# Boot_selector_SMD.net
KiCad netlist of a schematic drawn in EAGLE
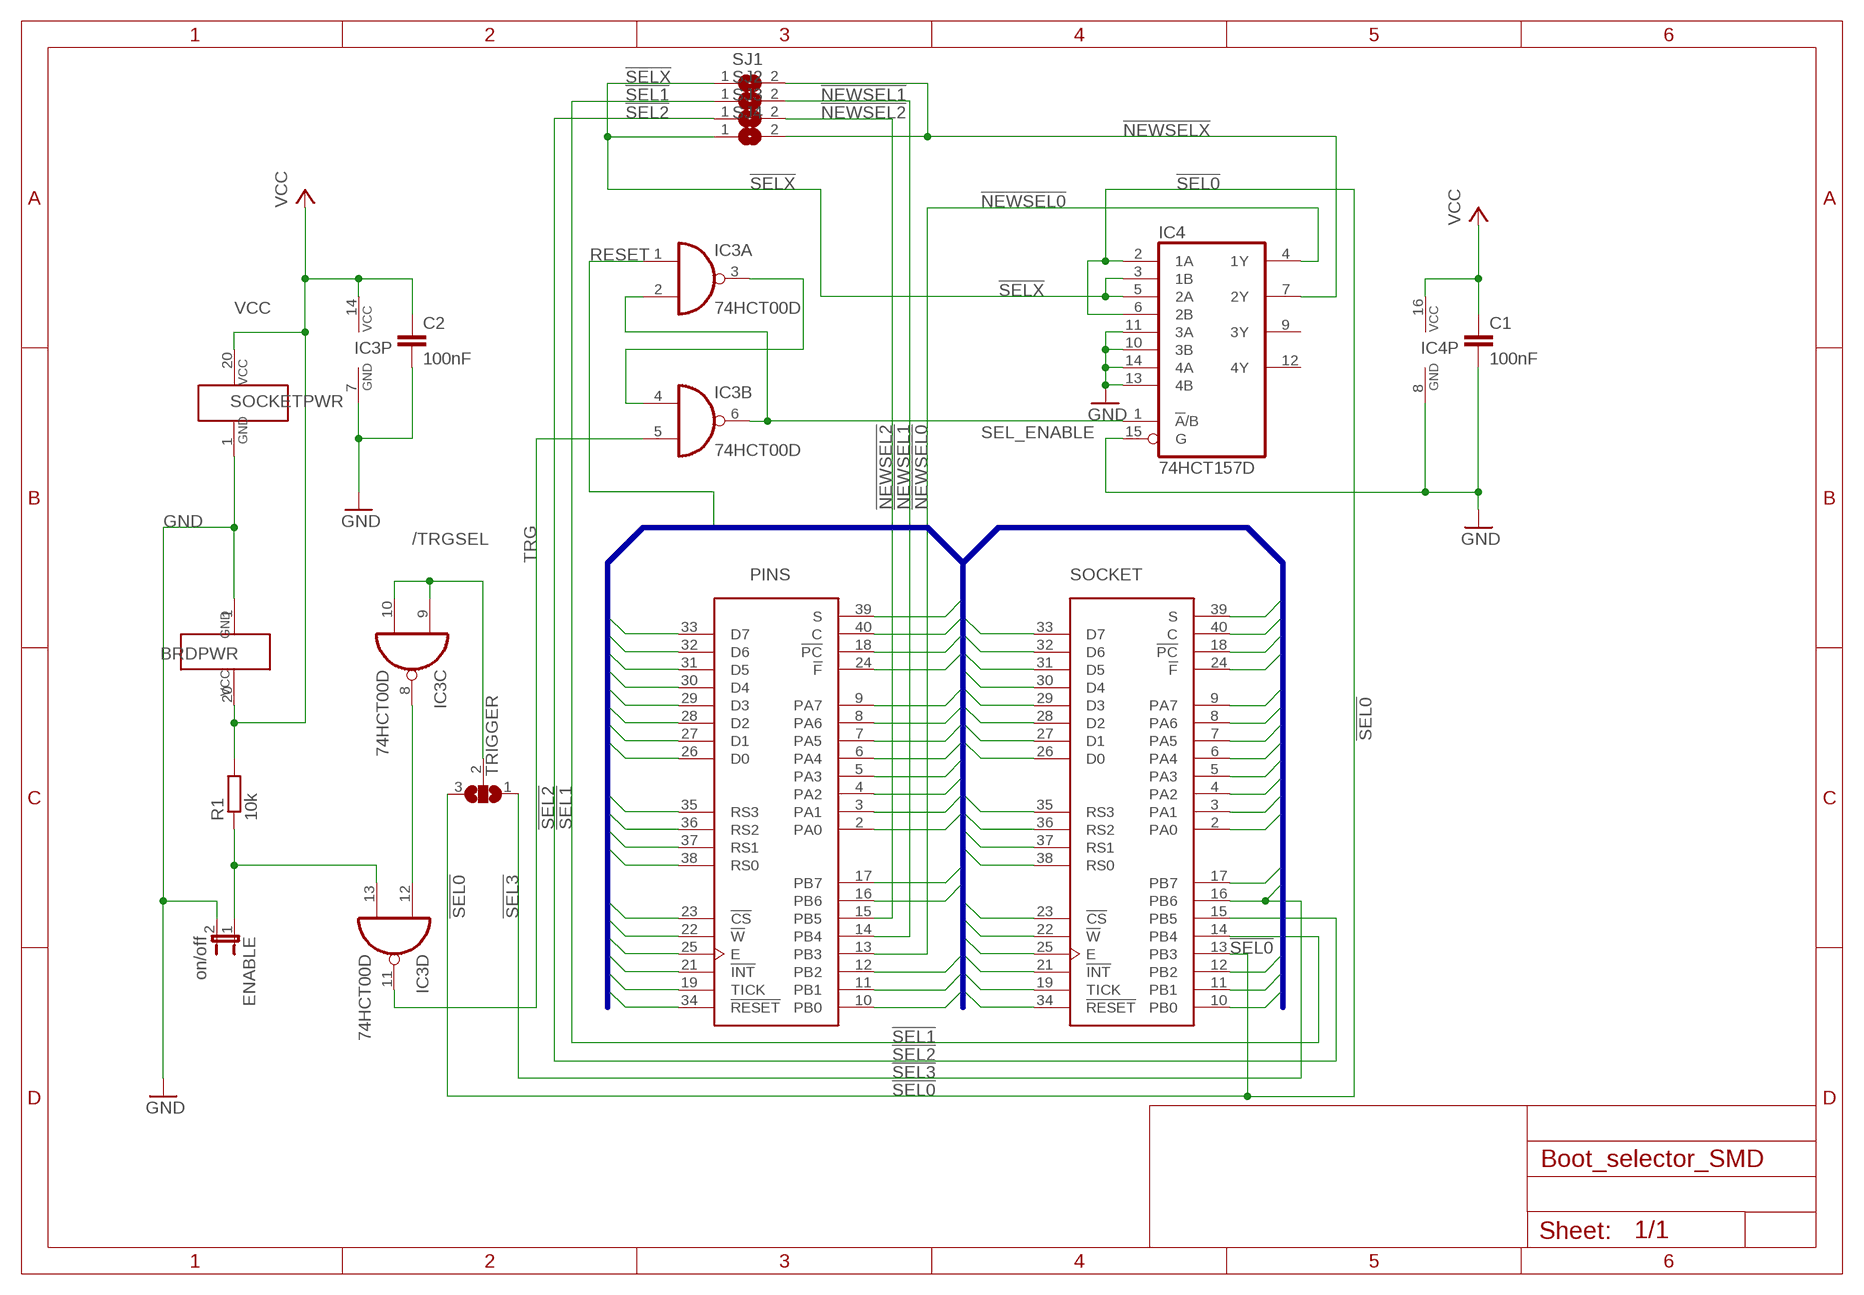
[diagram p0: schematic, sheet 1]

(export (version "E")
  (design (tool "Eeschema 10.0.6"))
  (components
    (comp (ref "BRD")
      (value "PINS")
      (footprint "eagle-import:DIP40-6")
      (libsource (lib "eagle-import") (part "CIA_DIP"))
    )
    (comp (ref "C1")
      (value "100nF")
      (footprint "eagle-import:C0805")
      (libsource (lib "eagle-import") (part "C-EUC0805"))
    )
    (comp (ref "C2")
      (value "100nF")
      (footprint "eagle-import:C0805K")
      (libsource (lib "eagle-import") (part "C-EUC0805K"))
    )
    (comp (ref "ENABLE")
      (value "on/off")
      (footprint "eagle-import:JP1")
      (libsource (lib "eagle-import") (part "JP1E"))
    )
    (comp (ref "IC3")
      (value "74HCT00D")
      (footprint "eagle-import:SO14")
      (libsource (lib "eagle-import") (part "7400DHCT"))
    )
    (comp (ref "IC4")
      (value "74HCT157D")
      (footprint "eagle-import:SO16")
      (libsource (lib "eagle-import") (part "74157DHCT"))
    )
    (comp (ref "R1")
      (value "10k")
      (footprint "eagle-import:R0805")
      (libsource (lib "eagle-import") (part "R-EU_R0805"))
    )
    (comp (ref "SJ1") (value "SJ") (footprint "eagle-import:SJ") (libsource (lib "eagle-import") (part "SJ")))
    (comp (ref "SJ2") (value "SJ") (footprint "eagle-import:SJ") (libsource (lib "eagle-import") (part "SJ")))
    (comp (ref "SJ3") (value "SJ") (footprint "eagle-import:SJ") (libsource (lib "eagle-import") (part "SJ")))
    (comp (ref "SJ4") (value "SJ") (footprint "eagle-import:SJ") (libsource (lib "eagle-import") (part "SJ")))
    (comp (ref "SOCKET")
      (value "CIA_DIP")
      (footprint "eagle-import:DIP40-6")
      (libsource (lib "eagle-import") (part "CIA_DIP"))
    )
    (comp (ref "TRIGGER")
      (value "SJ2W")
      (footprint "eagle-import:SJ_2")
      (libsource (lib "eagle-import") (part "SJ2W"))
    )
  )
  (nets
    (net (code "1") (name "/C") (class "Default")
      (node (ref "BRD") (pin "40") (pinfunction "C_40") (pintype "bidirectional"))
      (node (ref "SOCKET") (pin "40") (pinfunction "C_40") (pintype "bidirectional"))
    )
    (net (code "2") (name "/CS") (class "Default")
      (node (ref "BRD") (pin "23") (pinfunction "~{CS}_23") (pintype "input"))
      (node (ref "SOCKET") (pin "23") (pinfunction "~{CS}_23") (pintype "input"))
    )
    (net (code "3") (name "/D0") (class "Default")
      (node (ref "BRD") (pin "26") (pinfunction "D0_26") (pintype "bidirectional"))
      (node (ref "SOCKET") (pin "26") (pinfunction "D0_26") (pintype "bidirectional"))
    )
    (net (code "4") (name "/D1") (class "Default")
      (node (ref "BRD") (pin "27") (pinfunction "D1_27") (pintype "bidirectional"))
      (node (ref "SOCKET") (pin "27") (pinfunction "D1_27") (pintype "bidirectional"))
    )
    (net (code "5") (name "/D2") (class "Default")
      (node (ref "BRD") (pin "28") (pinfunction "D2_28") (pintype "bidirectional"))
      (node (ref "SOCKET") (pin "28") (pinfunction "D2_28") (pintype "bidirectional"))
    )
    (net (code "6") (name "/D3") (class "Default")
      (node (ref "BRD") (pin "29") (pinfunction "D3_29") (pintype "bidirectional"))
      (node (ref "SOCKET") (pin "29") (pinfunction "D3_29") (pintype "bidirectional"))
    )
    (net (code "7") (name "/D4") (class "Default")
      (node (ref "BRD") (pin "30") (pinfunction "D4_30") (pintype "bidirectional"))
      (node (ref "SOCKET") (pin "30") (pinfunction "D4_30") (pintype "bidirectional"))
    )
    (net (code "8") (name "/D5") (class "Default")
      (node (ref "BRD") (pin "31") (pinfunction "D5_31") (pintype "bidirectional"))
      (node (ref "SOCKET") (pin "31") (pinfunction "D5_31") (pintype "bidirectional"))
    )
    (net (code "9") (name "/D6") (class "Default")
      (node (ref "BRD") (pin "32") (pinfunction "D6_32") (pintype "bidirectional"))
      (node (ref "SOCKET") (pin "32") (pinfunction "D6_32") (pintype "bidirectional"))
    )
    (net (code "10") (name "/D7") (class "Default")
      (node (ref "BRD") (pin "33") (pinfunction "D7_33") (pintype "bidirectional"))
      (node (ref "SOCKET") (pin "33") (pinfunction "D7_33") (pintype "bidirectional"))
    )
    (net (code "11") (name "/E") (class "Default")
      (node (ref "BRD") (pin "25") (pinfunction "E_25") (pintype "input"))
      (node (ref "SOCKET") (pin "25") (pinfunction "E_25") (pintype "input"))
    )
    (net (code "12") (name "/F") (class "Default")
      (node (ref "BRD") (pin "24") (pinfunction "~{F}_24") (pintype "bidirectional"))
      (node (ref "SOCKET") (pin "24") (pinfunction "~{F}_24") (pintype "bidirectional"))
    )
    (net (code "13") (name "/INT") (class "Default")
      (node (ref "BRD") (pin "21") (pinfunction "~{INT}_21") (pintype "output"))
      (node (ref "SOCKET") (pin "21") (pinfunction "~{INT}_21") (pintype "output"))
    )
    (net (code "14") (name "/PA0") (class "Default")
      (node (ref "BRD") (pin "2") (pinfunction "PA0_2") (pintype "bidirectional"))
      (node (ref "SOCKET") (pin "2") (pinfunction "PA0_2") (pintype "bidirectional"))
    )
    (net (code "15") (name "/PA1") (class "Default")
      (node (ref "BRD") (pin "3") (pinfunction "PA1_3") (pintype "bidirectional"))
      (node (ref "SOCKET") (pin "3") (pinfunction "PA1_3") (pintype "bidirectional"))
    )
    (net (code "16") (name "/PA2") (class "Default")
      (node (ref "BRD") (pin "4") (pinfunction "PA2_4") (pintype "bidirectional"))
      (node (ref "SOCKET") (pin "4") (pinfunction "PA2_4") (pintype "bidirectional"))
    )
    (net (code "17") (name "/PA3") (class "Default")
      (node (ref "BRD") (pin "5") (pinfunction "PA3_5") (pintype "bidirectional"))
      (node (ref "SOCKET") (pin "5") (pinfunction "PA3_5") (pintype "bidirectional"))
    )
    (net (code "18") (name "/PA4") (class "Default")
      (node (ref "BRD") (pin "6") (pinfunction "PA4_6") (pintype "bidirectional"))
      (node (ref "SOCKET") (pin "6") (pinfunction "PA4_6") (pintype "bidirectional"))
    )
    (net (code "19") (name "/PA5") (class "Default")
      (node (ref "BRD") (pin "7") (pinfunction "PA5_7") (pintype "bidirectional"))
      (node (ref "SOCKET") (pin "7") (pinfunction "PA5_7") (pintype "bidirectional"))
    )
    (net (code "20") (name "/PA6") (class "Default")
      (node (ref "BRD") (pin "8") (pinfunction "PA6_8") (pintype "bidirectional"))
      (node (ref "SOCKET") (pin "8") (pinfunction "PA6_8") (pintype "bidirectional"))
    )
    (net (code "21") (name "/PA7") (class "Default")
      (node (ref "BRD") (pin "9") (pinfunction "PA7_9") (pintype "bidirectional"))
      (node (ref "SOCKET") (pin "9") (pinfunction "PA7_9") (pintype "bidirectional"))
    )
    (net (code "22") (name "/PB0") (class "Default")
      (node (ref "BRD") (pin "10") (pinfunction "PB0_10") (pintype "bidirectional"))
      (node (ref "SOCKET") (pin "10") (pinfunction "PB0_10") (pintype "bidirectional"))
    )
    (net (code "23") (name "/PB1") (class "Default")
      (node (ref "BRD") (pin "11") (pinfunction "PB1_11") (pintype "bidirectional"))
      (node (ref "SOCKET") (pin "11") (pinfunction "PB1_11") (pintype "bidirectional"))
    )
    (net (code "24") (name "/PB2") (class "Default")
      (node (ref "BRD") (pin "12") (pinfunction "PB2_12") (pintype "bidirectional"))
      (node (ref "SOCKET") (pin "12") (pinfunction "PB2_12") (pintype "bidirectional"))
    )
    (net (code "25") (name "/PB7") (class "Default")
      (node (ref "BRD") (pin "17") (pinfunction "PB7_17") (pintype "bidirectional"))
      (node (ref "SOCKET") (pin "17") (pinfunction "PB7_17") (pintype "bidirectional"))
    )
    (net (code "26") (name "/PC") (class "Default")
      (node (ref "BRD") (pin "18") (pinfunction "~{PC}_18") (pintype "bidirectional"))
      (node (ref "SOCKET") (pin "18") (pinfunction "~{PC}_18") (pintype "bidirectional"))
    )
    (net (code "27") (name "/RESET") (class "Default")
      (node (ref "BRD") (pin "34") (pinfunction "~{RESET}_34") (pintype "input"))
      (node (ref "IC3") (pin "1") (pinfunction "I0_1") (pintype "input"))
      (node (ref "SOCKET") (pin "34") (pinfunction "~{RESET}_34") (pintype "input"))
    )
    (net (code "28") (name "/RS0") (class "Default")
      (node (ref "BRD") (pin "38") (pinfunction "RS0_38") (pintype "input"))
      (node (ref "SOCKET") (pin "38") (pinfunction "RS0_38") (pintype "input"))
    )
    (net (code "29") (name "/RS1") (class "Default")
      (node (ref "BRD") (pin "37") (pinfunction "RS1_37") (pintype "input"))
      (node (ref "SOCKET") (pin "37") (pinfunction "RS1_37") (pintype "input"))
    )
    (net (code "30") (name "/RS2") (class "Default")
      (node (ref "BRD") (pin "36") (pinfunction "RS2_36") (pintype "input"))
      (node (ref "SOCKET") (pin "36") (pinfunction "RS2_36") (pintype "input"))
    )
    (net (code "31") (name "/RS3") (class "Default")
      (node (ref "BRD") (pin "35") (pinfunction "RS3_35") (pintype "input"))
      (node (ref "SOCKET") (pin "35") (pinfunction "RS3_35") (pintype "input"))
    )
    (net (code "32") (name "/S") (class "Default")
      (node (ref "BRD") (pin "39") (pinfunction "S_39") (pintype "bidirectional"))
      (node (ref "SOCKET") (pin "39") (pinfunction "S_39") (pintype "bidirectional"))
    )
    (net (code "33") (name "/SEL_ENABLE") (class "Default")
      (node (ref "IC3") (pin "2") (pinfunction "I1_2") (pintype "input"))
      (node (ref "IC3") (pin "6") (pinfunction "O_6") (pintype "output"))
      (node (ref "IC4") (pin "1") (pinfunction "~{A}/B_1") (pintype "input"))
    )
    (net (code "34") (name "/TICK") (class "Default")
      (node (ref "BRD") (pin "19") (pinfunction "TICK_19") (pintype "input"))
      (node (ref "SOCKET") (pin "19") (pinfunction "TICK_19") (pintype "input"))
    )
    (net (code "35") (name "/TRG") (class "Default")
      (node (ref "IC3") (pin "11") (pinfunction "O_11") (pintype "output"))
      (node (ref "IC3") (pin "5") (pinfunction "I1_5") (pintype "input"))
    )
    (net (code "36") (name "/W") (class "Default")
      (node (ref "BRD") (pin "22") (pinfunction "~{W}_22") (pintype "input"))
      (node (ref "SOCKET") (pin "22") (pinfunction "~{W}_22") (pintype "input"))
    )
    (net (code "37") (name "/{slash}TRGSEL") (class "Default")
      (node (ref "IC3") (pin "10") (pinfunction "I1_10") (pintype "input"))
      (node (ref "IC3") (pin "9") (pinfunction "I0_9") (pintype "input"))
      (node (ref "TRIGGER") (pin "2") (pinfunction "2_2") (pintype "passive"))
    )
    (net (code "38") (name "/~{NEWSEL0}") (class "Default")
      (node (ref "BRD") (pin "13") (pinfunction "PB3_13") (pintype "bidirectional"))
      (node (ref "IC4") (pin "4") (pinfunction "1Y_4") (pintype "output"))
    )
    (net (code "39") (name "/~{NEWSEL1}") (class "Default")
      (node (ref "BRD") (pin "14") (pinfunction "PB4_14") (pintype "bidirectional"))
      (node (ref "SJ2") (pin "2") (pinfunction "2_2") (pintype "passive"))
    )
    (net (code "40") (name "/~{NEWSEL2}") (class "Default")
      (node (ref "BRD") (pin "15") (pinfunction "PB5_15") (pintype "bidirectional"))
      (node (ref "SJ3") (pin "2") (pinfunction "2_2") (pintype "passive"))
    )
    (net (code "41") (name "/~{NEWSELX}") (class "Default")
      (node (ref "IC4") (pin "7") (pinfunction "2Y_7") (pintype "output"))
      (node (ref "SJ1") (pin "2") (pinfunction "2_2") (pintype "passive"))
      (node (ref "SJ4") (pin "2") (pinfunction "2_2") (pintype "passive"))
    )
    (net (code "42") (name "/~{SEL0}") (class "Default")
      (node (ref "IC4") (pin "2") (pinfunction "1A_2") (pintype "input"))
      (node (ref "IC4") (pin "6") (pinfunction "2B_6") (pintype "input"))
      (node (ref "SOCKET") (pin "13") (pinfunction "PB3_13") (pintype "bidirectional"))
      (node (ref "TRIGGER") (pin "3") (pinfunction "3_3") (pintype "passive"))
    )
    (net (code "43") (name "/~{SEL1}") (class "Default")
      (node (ref "SJ2") (pin "1") (pinfunction "1_1") (pintype "passive"))
      (node (ref "SOCKET") (pin "14") (pinfunction "PB4_14") (pintype "bidirectional"))
    )
    (net (code "44") (name "/~{SEL2}") (class "Default")
      (node (ref "SJ3") (pin "1") (pinfunction "1_1") (pintype "passive"))
      (node (ref "SOCKET") (pin "15") (pinfunction "PB5_15") (pintype "bidirectional"))
    )
    (net (code "45") (name "/~{SEL3}") (class "Default")
      (node (ref "BRD") (pin "16") (pinfunction "PB6_16") (pintype "bidirectional"))
      (node (ref "SOCKET") (pin "16") (pinfunction "PB6_16") (pintype "bidirectional"))
      (node (ref "TRIGGER") (pin "1") (pinfunction "1_1") (pintype "passive"))
    )
    (net (code "46") (name "/~{SELX}") (class "Default")
      (node (ref "IC4") (pin "3") (pinfunction "1B_3") (pintype "input"))
      (node (ref "IC4") (pin "5") (pinfunction "2A_5") (pintype "input"))
      (node (ref "SJ1") (pin "1") (pinfunction "1_1") (pintype "passive"))
      (node (ref "SJ4") (pin "1") (pinfunction "1_1") (pintype "passive"))
    )
    (net (code "47") (name "GND") (class "Default")
      (node (ref "BRD") (pin "1") (pinfunction "GND1_1") (pintype "power_in"))
      (node (ref "C1") (pin "2") (pinfunction "2_2") (pintype "passive"))
      (node (ref "C2") (pin "2") (pinfunction "2_2") (pintype "passive"))
      (node (ref "ENABLE") (pin "2") (pinfunction "2_2") (pintype "passive"))
      (node (ref "IC3") (pin "7") (pinfunction "GND_7") (pintype "power_in"))
      (node (ref "IC4") (pin "10") (pinfunction "3B_10") (pintype "input"))
      (node (ref "IC4") (pin "11") (pinfunction "3A_11") (pintype "input"))
      (node (ref "IC4") (pin "13") (pinfunction "4B_13") (pintype "input"))
      (node (ref "IC4") (pin "14") (pinfunction "4A_14") (pintype "input"))
      (node (ref "IC4") (pin "15") (pinfunction "G_15") (pintype "input"))
      (node (ref "IC4") (pin "8") (pinfunction "GND_8") (pintype "power_in"))
      (node (ref "SOCKET") (pin "1") (pinfunction "GND1_1") (pintype "power_in"))
    )
    (net (code "48") (name "Net-(IC3A-O)") (class "Default")
      (node (ref "IC3") (pin "3") (pinfunction "O_3") (pintype "output"))
      (node (ref "IC3") (pin "4") (pinfunction "I0_4") (pintype "input"))
    )
    (net (code "49") (name "Net-(IC3C-O)") (class "Default")
      (node (ref "IC3") (pin "12") (pinfunction "I0_12") (pintype "input"))
      (node (ref "IC3") (pin "8") (pinfunction "O_8") (pintype "output"))
    )
    (net (code "50") (name "Net-(IC3D-I1)") (class "Default")
      (node (ref "ENABLE") (pin "1") (pinfunction "1_1") (pintype "passive"))
      (node (ref "IC3") (pin "13") (pinfunction "I1_13") (pintype "input"))
      (node (ref "R1") (pin "1") (pinfunction "1_1") (pintype "passive"))
    )
    (net (code "51") (name "VCC") (class "Default")
      (node (ref "BRD") (pin "20") (pinfunction "VCC1_20") (pintype "power_in"))
      (node (ref "C1") (pin "1") (pinfunction "1_1") (pintype "passive"))
      (node (ref "C2") (pin "1") (pinfunction "1_1") (pintype "passive"))
      (node (ref "IC3") (pin "14") (pinfunction "VCC_14") (pintype "power_in"))
      (node (ref "IC4") (pin "16") (pinfunction "VCC_16") (pintype "power_in"))
      (node (ref "R1") (pin "2") (pinfunction "2_2") (pintype "passive"))
      (node (ref "SOCKET") (pin "20") (pinfunction "VCC1_20") (pintype "power_in"))
    )
    (net (code "52") (name "unconnected-(IC4A-3Y-Pad9)") (class "Default")
      (node (ref "IC4") (pin "9") (pinfunction "3Y_9") (pintype "output"))
    )
    (net (code "53") (name "unconnected-(IC4A-4Y-Pad12)") (class "Default")
      (node (ref "IC4") (pin "12") (pinfunction "4Y_12") (pintype "output"))
    )
  )
)
